# Qwiic_MP3_Trigger.net
KiCad netlist of a schematic drawn in EAGLE
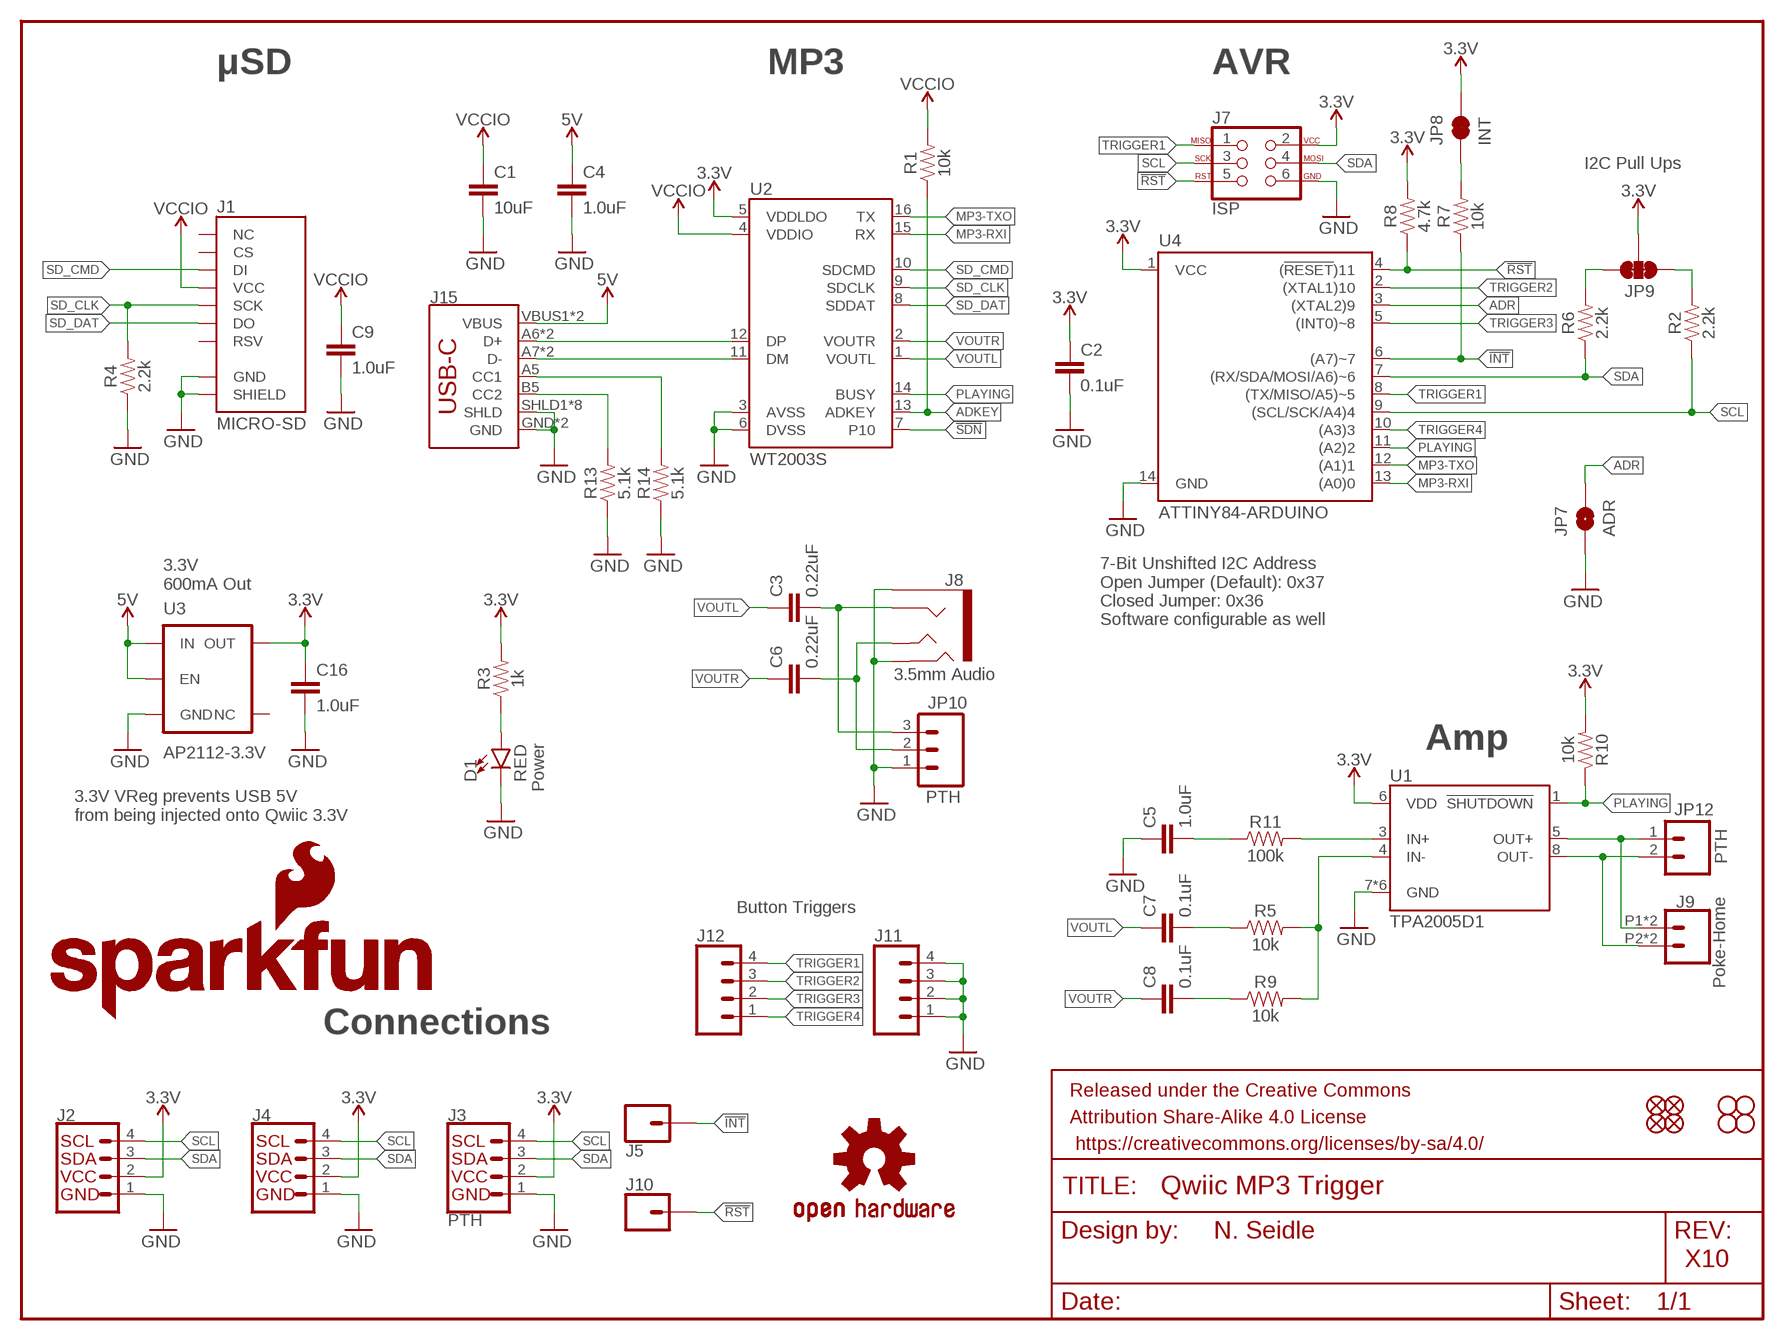
[diagram p0: schematic, sheet 1]

(export (version "E")
  (design (tool "Eeschema 10.0.6"))
  (components
    (comp (ref "C1")
      (value "10uF")
      (footprint "eagle-import:0603")
      (libsource (lib "eagle-import") (part "10UF-0603-6.3V-20%"))
    )
    (comp (ref "C2")
      (value "0.1uF")
      (footprint "eagle-import:0603")
      (libsource (lib "eagle-import") (part "0.1UF-0603-25V-(+80/-20%)"))
    )
    (comp (ref "C3")
      (value "0.22uF")
      (footprint "eagle-import:0603")
      (libsource (lib "eagle-import") (part "0.22UF-0603-25V-10%"))
    )
    (comp (ref "C4")
      (value "1.0uF")
      (footprint "eagle-import:0603")
      (libsource (lib "eagle-import") (part "1.0UF-0603-16V-10%"))
    )
    (comp (ref "C5")
      (value "1.0uF")
      (footprint "eagle-import:0603")
      (libsource (lib "eagle-import") (part "1.0UF-0603-16V-10%"))
    )
    (comp (ref "C6")
      (value "0.22uF")
      (footprint "eagle-import:0603")
      (libsource (lib "eagle-import") (part "0.22UF-0603-25V-10%"))
    )
    (comp (ref "C7")
      (value "0.1uF")
      (footprint "eagle-import:0603")
      (libsource (lib "eagle-import") (part "0.1UF-0603-25V-(+80/-20%)"))
    )
    (comp (ref "C8")
      (value "0.1uF")
      (footprint "eagle-import:0603")
      (libsource (lib "eagle-import") (part "0.1UF-0603-25V-(+80/-20%)"))
    )
    (comp (ref "C9")
      (value "1.0uF")
      (footprint "eagle-import:0603")
      (libsource (lib "eagle-import") (part "1.0UF-0603-16V-10%"))
    )
    (comp (ref "C16")
      (value "1.0uF")
      (footprint "eagle-import:0603")
      (libsource (lib "eagle-import") (part "1.0UF-0603-16V-10%"))
    )
    (comp (ref "D1")
      (value "RED")
      (footprint "eagle-import:LED-0603")
      (libsource (lib "eagle-import") (part "LED-RED0603"))
    )
    (comp (ref "FRAME1")
      (value "FRAME-LETTER")
      (footprint "eagle-import:CREATIVE_COMMONS")
      (libsource (lib "eagle-import") (part "FRAME-LETTER"))
    )
    (comp (ref "J1")
      (value "MICRO-SD")
      (footprint "eagle-import:MICRO-SD-SOCKET")
      (libsource (lib "eagle-import") (part "MICRO-SD_CARD_SOCKETPUSH-PUSH"))
    )
    (comp (ref "J2")
      (value "QWIIC_CONNECTORJS-1MM")
      (footprint "eagle-import:1X04_1MM_RA")
      (libsource (lib "eagle-import") (part "QWIIC_CONNECTORJS-1MM"))
    )
    (comp (ref "J3")
      (value "PTH")
      (footprint "eagle-import:1X04_NO_SILK")
      (libsource (lib "eagle-import") (part "I2C_STANDARD_NO_SILK"))
    )
    (comp (ref "J4")
      (value "QWIIC_CONNECTORJS-1MM")
      (footprint "eagle-import:1X04_1MM_RA")
      (libsource (lib "eagle-import") (part "QWIIC_CONNECTORJS-1MM"))
    )
    (comp (ref "J5")
      (value "CONN_01PTH_NO_SILK_YES_STOP")
      (footprint "eagle-import:1X01_NO_SILK")
      (libsource (lib "eagle-import") (part "CONN_01PTH_NO_SILK_YES_STOP"))
    )
    (comp (ref "J7")
      (value "ISP")
      (footprint "eagle-import:2X3_TEST_POINTS")
      (libsource (lib "eagle-import") (part "AVR_SPI_PROG_3X2TESTPOINTS"))
    )
    (comp (ref "J8")
      (value "3.5mm Audio")
      (footprint "eagle-import:AUDIO_JACK_3.5MM_TRRS_SMD_RA")
      (libsource (lib "eagle-import") (part "AUDIO_JACK_TRRSSMD_RA"))
    )
    (comp (ref "J9")
      (value "Poke-Home")
      (footprint "eagle-import:1X02_POKEHOME")
      (libsource (lib "eagle-import") (part "CONN_02SMALL_POKEHOME"))
    )
    (comp (ref "J10")
      (value "CONN_01PTH_NO_SILK_YES_STOP")
      (footprint "eagle-import:1X01_NO_SILK")
      (libsource (lib "eagle-import") (part "CONN_01PTH_NO_SILK_YES_STOP"))
    )
    (comp (ref "J11")
      (value "CONN_041X04_NO_SILK")
      (footprint "eagle-import:1X04_NO_SILK")
      (libsource (lib "eagle-import") (part "CONN_041X04_NO_SILK"))
    )
    (comp (ref "J12")
      (value "CONN_041X04_NO_SILK")
      (footprint "eagle-import:1X04_NO_SILK")
      (libsource (lib "eagle-import") (part "CONN_041X04_NO_SILK"))
    )
    (comp (ref "J15")
      (value "USB_C16PIN")
      (footprint "eagle-import:USB-C-16P")
      (libsource (lib "eagle-import") (part "USB_C16PIN"))
    )
    (comp (ref "JP1")
      (value "FIDUCIALUFIDUCIAL")
      (footprint "eagle-import:MICRO-FIDUCIAL")
      (libsource (lib "eagle-import") (part "FIDUCIALUFIDUCIAL"))
    )
    (comp (ref "JP2")
      (value "FIDUCIALUFIDUCIAL")
      (footprint "eagle-import:MICRO-FIDUCIAL")
      (libsource (lib "eagle-import") (part "FIDUCIALUFIDUCIAL"))
    )
    (comp (ref "JP3")
      (value "STAND-OFF")
      (footprint "eagle-import:STAND-OFF")
      (libsource (lib "eagle-import") (part "STAND-OFF"))
    )
    (comp (ref "JP4")
      (value "STAND-OFF")
      (footprint "eagle-import:STAND-OFF")
      (libsource (lib "eagle-import") (part "STAND-OFF"))
    )
    (comp (ref "JP5")
      (value "FIDUCIALUFIDUCIAL")
      (footprint "eagle-import:MICRO-FIDUCIAL")
      (libsource (lib "eagle-import") (part "FIDUCIALUFIDUCIAL"))
    )
    (comp (ref "JP6")
      (value "FIDUCIALUFIDUCIAL")
      (footprint "eagle-import:MICRO-FIDUCIAL")
      (libsource (lib "eagle-import") (part "FIDUCIALUFIDUCIAL"))
    )
    (comp (ref "JP7")
      (value "ADR")
      (footprint "eagle-import:SMT-JUMPER_2_NO_SILK")
      (libsource (lib "eagle-import") (part "JUMPER-SMT_2_NO_SILK"))
    )
    (comp (ref "JP8")
      (value "INT")
      (footprint "eagle-import:SMT-JUMPER_2_NC_TRACE_SILK")
      (libsource (lib "eagle-import") (part "JUMPER-SMT_2_NC_TRACE_SILK"))
    )
    (comp (ref "JP9")
      (value "JUMPER-SMT_3_2-NC_TRACE_SILK")
      (footprint "eagle-import:SMT-JUMPER_3_2-NC_TRACE_SILK")
      (libsource (lib "eagle-import") (part "JUMPER-SMT_3_2-NC_TRACE_SILK"))
    )
    (comp (ref "JP10")
      (value "PTH")
      (footprint "eagle-import:1X03_NO_SILK")
      (libsource (lib "eagle-import") (part "CONN_031X03_NO_SILK"))
    )
    (comp (ref "JP11")
      (value "STAND-OFF")
      (footprint "eagle-import:STAND-OFF")
      (libsource (lib "eagle-import") (part "STAND-OFF"))
    )
    (comp (ref "JP12")
      (value "PTH")
      (footprint "eagle-import:1X02_NO_SILK")
      (libsource (lib "eagle-import") (part "CONN_021X02_NO_SILK"))
    )
    (comp (ref "JP13")
      (value "STAND-OFF")
      (footprint "eagle-import:STAND-OFF")
      (libsource (lib "eagle-import") (part "STAND-OFF"))
    )
    (comp (ref "LOGO1")
      (value "OSHW-LOGOMINI")
      (footprint "eagle-import:OSHW-LOGO-MINI")
      (libsource (lib "eagle-import") (part "OSHW-LOGOMINI"))
    )
    (comp (ref "LOGO2")
      (value "SFE_LOGO_NAME.1_INCH")
      (footprint "eagle-import:SFE_LOGO_NAME_.1")
      (libsource (lib "eagle-import") (part "SFE_LOGO_NAME.1_INCH"))
    )
    (comp (ref "LOGO3")
      (value "SFE_LOGO_NAME_FLAME.1_INCH")
      (footprint "eagle-import:SFE_LOGO_NAME_FLAME_.1")
      (libsource (lib "eagle-import") (part "SFE_LOGO_NAME_FLAME.1_INCH"))
    )
    (comp (ref "R1")
      (value "10k")
      (footprint "eagle-import:0603")
      (libsource (lib "eagle-import") (part "10KOHM-0603-1/10W-1%"))
    )
    (comp (ref "R2")
      (value "2.2k")
      (footprint "eagle-import:0603")
      (libsource (lib "eagle-import") (part "2.2KOHM-0603-1/10W-1%"))
    )
    (comp (ref "R3")
      (value "1k")
      (footprint "eagle-import:0603")
      (libsource (lib "eagle-import") (part "1KOHM-0603-1/10W-1%"))
    )
    (comp (ref "R4")
      (value "2.2k")
      (footprint "eagle-import:0603")
      (libsource (lib "eagle-import") (part "2.2KOHM-0603-1/10W-1%"))
    )
    (comp (ref "R5")
      (value "10k")
      (footprint "eagle-import:0603")
      (libsource (lib "eagle-import") (part "10KOHM-0603-1/10W-1%"))
    )
    (comp (ref "R6")
      (value "2.2k")
      (footprint "eagle-import:0603")
      (libsource (lib "eagle-import") (part "2.2KOHM-0603-1/10W-1%"))
    )
    (comp (ref "R7")
      (value "10k")
      (footprint "eagle-import:0603")
      (libsource (lib "eagle-import") (part "10KOHM-0603-1/10W-1%"))
    )
    (comp (ref "R8")
      (value "4.7k")
      (footprint "eagle-import:0603")
      (libsource (lib "eagle-import") (part "4.7KOHM-0603-1/10W-1%"))
    )
    (comp (ref "R9")
      (value "10k")
      (footprint "eagle-import:0603")
      (libsource (lib "eagle-import") (part "10KOHM-0603-1/10W-1%"))
    )
    (comp (ref "R10")
      (value "10k")
      (footprint "eagle-import:0603")
      (libsource (lib "eagle-import") (part "10KOHM-0603-1/10W-1%"))
    )
    (comp (ref "R11")
      (value "100k")
      (footprint "eagle-import:0603")
      (libsource (lib "eagle-import") (part "100KOHM-0603-1/10W-1%"))
    )
    (comp (ref "R13")
      (value "5.1k")
      (footprint "eagle-import:0603")
      (libsource (lib "eagle-import") (part "5.1KOHM5.1KOHM-0603-1/10W-1%"))
    )
    (comp (ref "R14")
      (value "5.1k")
      (footprint "eagle-import:0603")
      (libsource (lib "eagle-import") (part "5.1KOHM5.1KOHM-0603-1/10W-1%"))
    )
    (comp (ref "U1")
      (value "TPA2005D1")
      (footprint "eagle-import:QFN-8_PAD")
      (libsource (lib "eagle-import") (part "TPA2005D1DRB"))
    )
    (comp (ref "U2")
      (value "WT2003S")
      (footprint "eagle-import:SO16")
      (libsource (lib "eagle-import") (part "WT2003S"))
    )
    (comp (ref "U3")
      (value "AP2112-3.3V")
      (footprint "eagle-import:SOT23-5")
      (libsource (lib "eagle-import") (part "V_REG_AP2112K-3.3V"))
    )
    (comp (ref "U4")
      (value "ATTINY84-ARDUINO")
      (footprint "eagle-import:SO14")
      (libsource (lib "eagle-import") (part "ATTINY84-ARDUINO"))
    )
  )
  (nets
    (net (code "1") (name "/~{INT}") (class "Default")
      (node (ref "J5") (pin "1") (pinfunction "1_1") (pintype "passive"))
      (node (ref "R7") (pin "1") (pinfunction "1_1") (pintype "passive"))
      (node (ref "U4") (pin "6") (pinfunction "(A7)~{7}_6") (pintype "bidirectional"))
    )
    (net (code "2") (name "/~{RST}") (class "Default")
      (node (ref "J10") (pin "1") (pinfunction "1_1") (pintype "passive"))
      (node (ref "J7") (pin "5") (pinfunction "5_5") (pintype "passive"))
      (node (ref "R8") (pin "1") (pinfunction "1_1") (pintype "passive"))
      (node (ref "U4") (pin "4") (pinfunction "(~{RESET})11_4") (pintype "bidirectional"))
    )
    (net (code "3") (name "/~{SDN}") (class "Default")
      (node (ref "U2") (pin "7") (pinfunction "P10_7") (pintype "bidirectional"))
    )
    (net (code "4") (name "3.3V") (class "Default")
      (node (ref "C16") (pin "1") (pinfunction "1_1") (pintype "passive"))
      (node (ref "C2") (pin "1") (pinfunction "1_1") (pintype "passive"))
      (node (ref "J2") (pin "2") (pinfunction "2_2") (pintype "power_in"))
      (node (ref "J3") (pin "2") (pinfunction "VCC_2") (pintype "power_in"))
      (node (ref "J4") (pin "2") (pinfunction "2_2") (pintype "power_in"))
      (node (ref "J7") (pin "2") (pinfunction "2_2") (pintype "passive"))
      (node (ref "JP8") (pin "2") (pinfunction "2_2") (pintype "passive"))
      (node (ref "JP9") (pin "2") (pinfunction "2_2") (pintype "passive"))
      (node (ref "R10") (pin "2") (pinfunction "2_2") (pintype "passive"))
      (node (ref "R3") (pin "2") (pinfunction "2_2") (pintype "passive"))
      (node (ref "R8") (pin "2") (pinfunction "2_2") (pintype "passive"))
      (node (ref "U1") (pin "6") (pinfunction "VDD_6") (pintype "power_in"))
      (node (ref "U2") (pin "5") (pinfunction "VDDLDO_5") (pintype "bidirectional"))
      (node (ref "U3") (pin "5") (pinfunction "OUT_5") (pintype "passive"))
      (node (ref "U4") (pin "1") (pinfunction "VCC_1") (pintype "bidirectional"))
    )
    (net (code "5") (name "5V") (class "Default")
      (node (ref "C4") (pin "1") (pinfunction "1_1") (pintype "passive"))
      (node (ref "J15") (pin "VBUS1") (pinfunction "VBUS_VBUS1") (pintype "bidirectional"))
      (node (ref "J15") (pin "VBUS2") (pinfunction "VBUS_VBUS2") (pintype "bidirectional"))
      (node (ref "U3") (pin "1") (pinfunction "IN_1") (pintype "input"))
      (node (ref "U3") (pin "3") (pinfunction "EN_3") (pintype "input"))
    )
    (net (code "6") (name "ADKEY") (class "Default")
      (node (ref "R1") (pin "1") (pinfunction "1_1") (pintype "passive"))
      (node (ref "U2") (pin "13") (pinfunction "ADKEY_13") (pintype "bidirectional"))
    )
    (net (code "7") (name "ADR") (class "Default")
      (node (ref "JP7") (pin "2") (pinfunction "2_2") (pintype "passive"))
      (node (ref "U4") (pin "3") (pinfunction "(XTAL2)9_3") (pintype "bidirectional"))
    )
    (net (code "8") (name "GND") (class "Default")
      (node (ref "C1") (pin "2") (pinfunction "2_2") (pintype "passive"))
      (node (ref "C16") (pin "2") (pinfunction "2_2") (pintype "passive"))
      (node (ref "C2") (pin "2") (pinfunction "2_2") (pintype "passive"))
      (node (ref "C4") (pin "2") (pinfunction "2_2") (pintype "passive"))
      (node (ref "C5") (pin "1") (pinfunction "1_1") (pintype "passive"))
      (node (ref "C9") (pin "2") (pinfunction "2_2") (pintype "passive"))
      (node (ref "D1") (pin "C") (pinfunction "C_C") (pintype "passive"))
      (node (ref "J1") (pin "CD1") (pinfunction "SHIELD_CD1") (pintype "bidirectional"))
      (node (ref "J1") (pin "GND") (pinfunction "GND_GND") (pintype "bidirectional"))
      (node (ref "J11") (pin "1") (pinfunction "1_1") (pintype "passive"))
      (node (ref "J11") (pin "2") (pinfunction "2_2") (pintype "passive"))
      (node (ref "J11") (pin "3") (pinfunction "3_3") (pintype "passive"))
      (node (ref "J11") (pin "4") (pinfunction "4_4") (pintype "passive"))
      (node (ref "J15") (pin "GND") (pinfunction "GND_GND") (pintype "bidirectional"))
      (node (ref "J15") (pin "GND2") (pinfunction "GND_GND2") (pintype "bidirectional"))
      (node (ref "J15") (pin "SHLD1") (pinfunction "SHLD_SHLD1") (pintype "bidirectional"))
      (node (ref "J15") (pin "SHLD2") (pinfunction "SHLD_SHLD2") (pintype "bidirectional"))
      (node (ref "J15") (pin "SHLD3") (pinfunction "SHLD_SHLD3") (pintype "bidirectional"))
      (node (ref "J15") (pin "SHLD4") (pinfunction "SHLD_SHLD4") (pintype "bidirectional"))
      (node (ref "J15") (pin "SHLD5") (pinfunction "SHLD_SHLD5") (pintype "bidirectional"))
      (node (ref "J15") (pin "SHLD6") (pinfunction "SHLD_SHLD6") (pintype "bidirectional"))
      (node (ref "J15") (pin "SHLD7") (pinfunction "SHLD_SHLD7") (pintype "bidirectional"))
      (node (ref "J15") (pin "SHLD8") (pinfunction "SHLD_SHLD8") (pintype "bidirectional"))
      (node (ref "J2") (pin "1") (pinfunction "1_1") (pintype "power_in"))
      (node (ref "J3") (pin "1") (pinfunction "GND_1") (pintype "power_in"))
      (node (ref "J4") (pin "1") (pinfunction "1_1") (pintype "power_in"))
      (node (ref "J7") (pin "6") (pinfunction "6_6") (pintype "passive"))
      (node (ref "J8") (pin "EARTH") (pinfunction "EARTH_EARTH") (pintype "bidirectional"))
      (node (ref "J8") (pin "RING2") (pinfunction "RING2_RING2") (pintype "bidirectional"))
      (node (ref "JP10") (pin "1") (pinfunction "1_1") (pintype "passive"))
      (node (ref "JP7") (pin "1") (pinfunction "1_1") (pintype "passive"))
      (node (ref "R13") (pin "1") (pinfunction "1_1") (pintype "passive"))
      (node (ref "R14") (pin "1") (pinfunction "1_1") (pintype "passive"))
      (node (ref "R4") (pin "1") (pinfunction "1_1") (pintype "passive"))
      (node (ref "U1") (pin "10") (pinfunction "GND_10") (pintype "power_in"))
      (node (ref "U1") (pin "11") (pinfunction "GND_11") (pintype "power_in"))
      (node (ref "U1") (pin "12") (pinfunction "GND_12") (pintype "power_in"))
      (node (ref "U1") (pin "13") (pinfunction "GND_13") (pintype "power_in"))
      (node (ref "U1") (pin "7") (pinfunction "GND_7") (pintype "power_in"))
      (node (ref "U1") (pin "9") (pinfunction "GND_9") (pintype "power_in"))
      (node (ref "U2") (pin "3") (pinfunction "AVSS_3") (pintype "bidirectional"))
      (node (ref "U2") (pin "6") (pinfunction "DVSS_6") (pintype "bidirectional"))
      (node (ref "U3") (pin "2") (pinfunction "GND_2") (pintype "input"))
      (node (ref "U4") (pin "14") (pinfunction "GND_14") (pintype "bidirectional"))
    )
    (net (code "9") (name "MP3-RXI") (class "Default")
      (node (ref "U2") (pin "15") (pinfunction "RX_15") (pintype "bidirectional"))
      (node (ref "U4") (pin "13") (pinfunction "(A0)0_13") (pintype "bidirectional"))
    )
    (net (code "10") (name "MP3-TXO") (class "Default")
      (node (ref "U2") (pin "16") (pinfunction "TX_16") (pintype "bidirectional"))
      (node (ref "U4") (pin "12") (pinfunction "(A1)1_12") (pintype "bidirectional"))
    )
    (net (code "11") (name "Net-(C3-Pad2)") (class "Default")
      (node (ref "C3") (pin "2") (pinfunction "2_2") (pintype "passive"))
      (node (ref "J8") (pin "RING1") (pinfunction "RING1_RING1") (pintype "bidirectional"))
      (node (ref "JP10") (pin "3") (pinfunction "3_3") (pintype "passive"))
    )
    (net (code "12") (name "Net-(C5-Pad2)") (class "Default")
      (node (ref "C5") (pin "2") (pinfunction "2_2") (pintype "passive"))
      (node (ref "R11") (pin "1") (pinfunction "1_1") (pintype "passive"))
    )
    (net (code "13") (name "Net-(C6-Pad2)") (class "Default")
      (node (ref "C6") (pin "2") (pinfunction "2_2") (pintype "passive"))
      (node (ref "J8") (pin "TIP") (pinfunction "TIP_TIP") (pintype "bidirectional"))
      (node (ref "JP10") (pin "2") (pinfunction "2_2") (pintype "passive"))
    )
    (net (code "14") (name "Net-(C7-Pad2)") (class "Default")
      (node (ref "C7") (pin "2") (pinfunction "2_2") (pintype "passive"))
      (node (ref "R5") (pin "1") (pinfunction "1_1") (pintype "passive"))
    )
    (net (code "15") (name "Net-(C8-Pad2)") (class "Default")
      (node (ref "C8") (pin "2") (pinfunction "2_2") (pintype "passive"))
      (node (ref "R9") (pin "1") (pinfunction "1_1") (pintype "passive"))
    )
    (net (code "16") (name "Net-(D1-PadA)") (class "Default")
      (node (ref "D1") (pin "A") (pinfunction "A_A") (pintype "passive"))
      (node (ref "R3") (pin "1") (pinfunction "1_1") (pintype "passive"))
    )
    (net (code "17") (name "Net-(J15-CC1)") (class "Default")
      (node (ref "J15") (pin "A5") (pinfunction "CC1_A5") (pintype "bidirectional"))
      (node (ref "R14") (pin "2") (pinfunction "2_2") (pintype "passive"))
    )
    (net (code "18") (name "Net-(J15-CC2)") (class "Default")
      (node (ref "J15") (pin "B5") (pinfunction "CC2_B5") (pintype "bidirectional"))
      (node (ref "R13") (pin "2") (pinfunction "2_2") (pintype "passive"))
    )
    (net (code "19") (name "Net-(JP8-Pad1)") (class "Default")
      (node (ref "JP8") (pin "1") (pinfunction "1_1") (pintype "passive"))
      (node (ref "R7") (pin "2") (pinfunction "2_2") (pintype "passive"))
    )
    (net (code "20") (name "Net-(JP9-Pad1)") (class "Default")
      (node (ref "JP9") (pin "1") (pinfunction "1_1") (pintype "passive"))
      (node (ref "R2") (pin "2") (pinfunction "2_2") (pintype "passive"))
    )
    (net (code "21") (name "Net-(JP9-Pad3)") (class "Default")
      (node (ref "JP9") (pin "3") (pinfunction "3_3") (pintype "passive"))
      (node (ref "R6") (pin "2") (pinfunction "2_2") (pintype "passive"))
    )
    (net (code "22") (name "Net-(U1-IN+)") (class "Default")
      (node (ref "R11") (pin "2") (pinfunction "2_2") (pintype "passive"))
      (node (ref "U1") (pin "3") (pinfunction "IN+_3") (pintype "bidirectional"))
    )
    (net (code "23") (name "Net-(U1-IN-)") (class "Default")
      (node (ref "R5") (pin "2") (pinfunction "2_2") (pintype "passive"))
      (node (ref "R9") (pin "2") (pinfunction "2_2") (pintype "passive"))
      (node (ref "U1") (pin "4") (pinfunction "IN-_4") (pintype "bidirectional"))
    )
    (net (code "24") (name "Net-(U1-OUT+)") (class "Default")
      (node (ref "J9") (pin "P1") (pinfunction "1_P1") (pintype "passive"))
      (node (ref "J9") (pin "P3") (pinfunction "1_P3") (pintype "passive"))
      (node (ref "JP12") (pin "1") (pinfunction "1_1") (pintype "passive"))
      (node (ref "U1") (pin "5") (pinfunction "OUT+_5") (pintype "bidirectional"))
    )
    (net (code "25") (name "Net-(U1-OUT-)") (class "Default")
      (node (ref "J9") (pin "P2") (pinfunction "2_P2") (pintype "passive"))
      (node (ref "J9") (pin "P4") (pinfunction "2_P4") (pintype "passive"))
      (node (ref "JP12") (pin "2") (pinfunction "2_2") (pintype "passive"))
      (node (ref "U1") (pin "8") (pinfunction "OUT-_8") (pintype "bidirectional"))
    )
    (net (code "26") (name "Net-(U2-DM)") (class "Default")
      (node (ref "J15") (pin "A7") (pinfunction "D-_A7") (pintype "bidirectional"))
      (node (ref "J15") (pin "B7") (pinfunction "D-_B7") (pintype "bidirectional"))
      (node (ref "U2") (pin "11") (pinfunction "DM_11") (pintype "bidirectional"))
    )
    (net (code "27") (name "Net-(U2-DP)") (class "Default")
      (node (ref "J15") (pin "A6") (pinfunction "D+_A6") (pintype "bidirectional"))
      (node (ref "J15") (pin "B6") (pinfunction "D+_B6") (pintype "bidirectional"))
      (node (ref "U2") (pin "12") (pinfunction "DP_12") (pintype "bidirectional"))
    )
    (net (code "28") (name "PLAYING") (class "Default")
      (node (ref "R10") (pin "1") (pinfunction "1_1") (pintype "passive"))
      (node (ref "U1") (pin "1") (pinfunction "~{SHUTDOWN}_1") (pintype "input"))
      (node (ref "U2") (pin "14") (pinfunction "BUSY_14") (pintype "bidirectional"))
      (node (ref "U4") (pin "11") (pinfunction "(A2)2_11") (pintype "bidirectional"))
    )
    (net (code "29") (name "SCL") (class "Default")
      (node (ref "J2") (pin "4") (pinfunction "4_4") (pintype "passive"))
      (node (ref "J3") (pin "4") (pinfunction "SCL_4") (pintype "passive"))
      (node (ref "J4") (pin "4") (pinfunction "4_4") (pintype "passive"))
      (node (ref "J7") (pin "3") (pinfunction "3_3") (pintype "passive"))
      (node (ref "R2") (pin "1") (pinfunction "1_1") (pintype "passive"))
      (node (ref "U4") (pin "9") (pinfunction "(SCL/SCK/A4)4_9") (pintype "bidirectional"))
    )
    (net (code "30") (name "SDA") (class "Default")
      (node (ref "J2") (pin "3") (pinfunction "3_3") (pintype "passive"))
      (node (ref "J3") (pin "3") (pinfunction "SDA_3") (pintype "passive"))
      (node (ref "J4") (pin "3") (pinfunction "3_3") (pintype "passive"))
      (node (ref "J7") (pin "4") (pinfunction "4_4") (pintype "passive"))
      (node (ref "R6") (pin "1") (pinfunction "1_1") (pintype "passive"))
      (node (ref "U4") (pin "7") (pinfunction "(RX/SDA/MOSI/A6)~{6}_7") (pintype "bidirectional"))
    )
    (net (code "31") (name "SD_CLK") (class "Default")
      (node (ref "J1") (pin "SCLK") (pinfunction "SCK_SCLK") (pintype "bidirectional"))
      (node (ref "R4") (pin "2") (pinfunction "2_2") (pintype "passive"))
      (node (ref "U2") (pin "9") (pinfunction "SDCLK_9") (pintype "bidirectional"))
    )
    (net (code "32") (name "SD_CMD") (class "Default")
      (node (ref "J1") (pin "DI") (pinfunction "DI_DI") (pintype "bidirectional"))
      (node (ref "U2") (pin "10") (pinfunction "SDCMD_10") (pintype "bidirectional"))
    )
    (net (code "33") (name "SD_DAT") (class "Default")
      (node (ref "J1") (pin "DO") (pinfunction "DO_DO") (pintype "bidirectional"))
      (node (ref "U2") (pin "8") (pinfunction "SDDAT_8") (pintype "bidirectional"))
    )
    (net (code "34") (name "TRIGGER1") (class "Default")
      (node (ref "J12") (pin "4") (pinfunction "4_4") (pintype "passive"))
      (node (ref "J7") (pin "1") (pinfunction "1_1") (pintype "passive"))
      (node (ref "U4") (pin "8") (pinfunction "(TX/MISO/A5)~{5}_8") (pintype "bidirectional"))
    )
    (net (code "35") (name "TRIGGER2") (class "Default")
      (node (ref "J12") (pin "3") (pinfunction "3_3") (pintype "passive"))
      (node (ref "U4") (pin "2") (pinfunction "(XTAL1)10_2") (pintype "bidirectional"))
    )
    (net (code "36") (name "TRIGGER3") (class "Default")
      (node (ref "J12") (pin "2") (pinfunction "2_2") (pintype "passive"))
      (node (ref "U4") (pin "5") (pinfunction "(INT0)~{8}_5") (pintype "bidirectional"))
    )
    (net (code "37") (name "TRIGGER4") (class "Default")
      (node (ref "J12") (pin "1") (pinfunction "1_1") (pintype "passive"))
      (node (ref "U4") (pin "10") (pinfunction "(A3)3_10") (pintype "bidirectional"))
    )
    (net (code "38") (name "VCCIO") (class "Default")
      (node (ref "C1") (pin "1") (pinfunction "1_1") (pintype "passive"))
      (node (ref "C9") (pin "1") (pinfunction "1_1") (pintype "passive"))
      (node (ref "J1") (pin "VCC") (pinfunction "VCC_VCC") (pintype "bidirectional"))
      (node (ref "R1") (pin "2") (pinfunction "2_2") (pintype "passive"))
      (node (ref "U2") (pin "4") (pinfunction "VDDIO_4") (pintype "bidirectional"))
    )
    (net (code "39") (name "VOUTL") (class "Default")
      (node (ref "C3") (pin "1") (pinfunction "1_1") (pintype "passive"))
      (node (ref "C7") (pin "1") (pinfunction "1_1") (pintype "passive"))
      (node (ref "U2") (pin "1") (pinfunction "VOUTL_1") (pintype "bidirectional"))
    )
    (net (code "40") (name "VOUTR") (class "Default")
      (node (ref "C6") (pin "1") (pinfunction "1_1") (pintype "passive"))
      (node (ref "C8") (pin "1") (pinfunction "1_1") (pintype "passive"))
      (node (ref "U2") (pin "2") (pinfunction "VOUTR_2") (pintype "bidirectional"))
    )
    (net (code "41") (name "unconnected-(J1-NC-PadRSV2)") (class "Default")
      (node (ref "J1") (pin "RSV2") (pinfunction "NC_RSV2") (pintype "bidirectional"))
    )
    (net (code "42") (name "unconnected-(J1-PadCS)") (class "Default")
      (node (ref "J1") (pin "CS") (pinfunction "CS_CS") (pintype "bidirectional"))
    )
    (net (code "43") (name "unconnected-(J1-RSV-PadRSV1)") (class "Default")
      (node (ref "J1") (pin "RSV1") (pinfunction "RSV_RSV1") (pintype "bidirectional"))
    )
    (net (code "44") (name "unconnected-(U3-NC-Pad4)") (class "Default")
      (node (ref "U3") (pin "4") (pinfunction "NC_4") (pintype "input"))
    )
  )
)
